# Mezzanine.net
KiCad netlist of a schematic drawn in Altium Designer
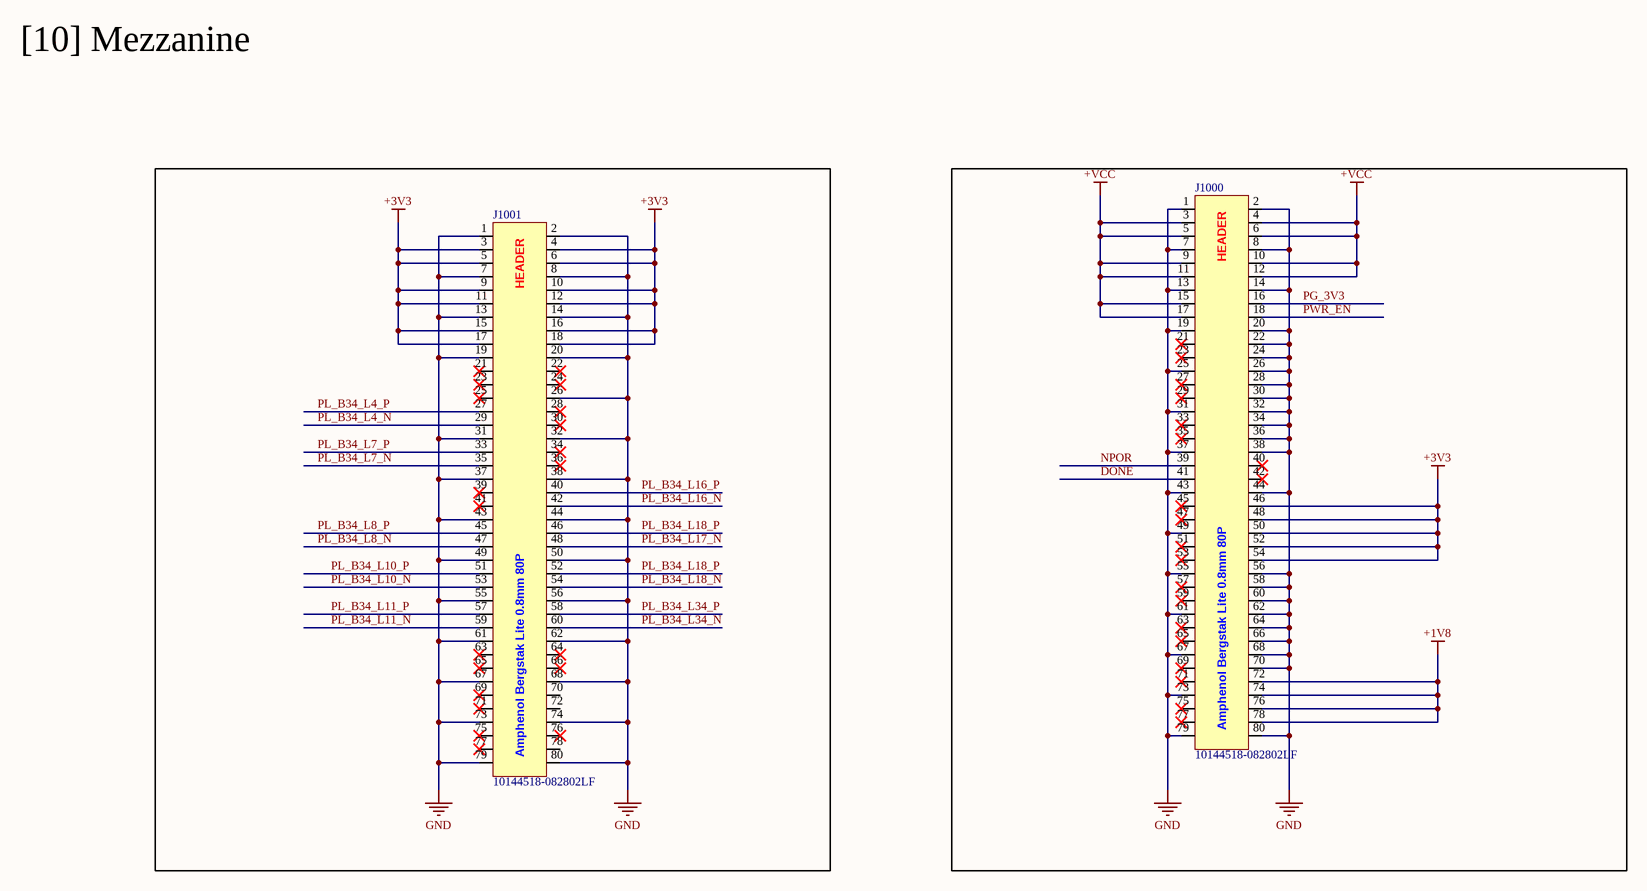
[diagram p0: Mezzanine.SchDoc]

(export (version "E")
  (design (tool "Eeschema 10.0.6"))
  (components
    (comp (ref "J1000")
      (value "10144518-082802LF")
      (footprint "10144518-082802LF")
      (description "BergStak® Lite 0.80mm, Board-to-Board Connector, 80 Positions, Dual Row, Vertical Header")
      (fields (field (name "MANUFACTURER") "Amphenol"))
      (libsource (lib "Schematic-Lib-PhilsLab") (part "10144518-082802LF"))
    )
    (comp (ref "J1001")
      (value "10144518-082802LF")
      (footprint "10144518-082802LF")
      (description "BergStak® Lite 0.80mm, Board-to-Board Connector, 80 Positions, Dual Row, Vertical Header")
      (fields (field (name "MANUFACTURER") "Amphenol"))
      (libsource (lib "Schematic-Lib-PhilsLab") (part "10144518-082802LF"))
    )
  )
  (nets
    (net (code "1") (name "+1V8") (class "Default")
      (node (ref "J1000") (pin "72") (pintype "passive"))
      (node (ref "J1000") (pin "74") (pintype "passive"))
      (node (ref "J1000") (pin "76") (pintype "passive"))
      (node (ref "J1000") (pin "78") (pintype "passive"))
    )
    (net (code "2") (name "+3V3") (class "Default")
      (node (ref "J1000") (pin "46") (pintype "passive"))
      (node (ref "J1000") (pin "48") (pintype "passive"))
      (node (ref "J1000") (pin "50") (pintype "passive"))
      (node (ref "J1000") (pin "52") (pintype "passive"))
      (node (ref "J1000") (pin "54") (pintype "passive"))
      (node (ref "J1001") (pin "10") (pintype "passive"))
      (node (ref "J1001") (pin "11") (pintype "passive"))
      (node (ref "J1001") (pin "12") (pintype "passive"))
      (node (ref "J1001") (pin "15") (pintype "passive"))
      (node (ref "J1001") (pin "16") (pintype "passive"))
      (node (ref "J1001") (pin "17") (pintype "passive"))
      (node (ref "J1001") (pin "18") (pintype "passive"))
      (node (ref "J1001") (pin "3") (pintype "passive"))
      (node (ref "J1001") (pin "4") (pintype "passive"))
      (node (ref "J1001") (pin "5") (pintype "passive"))
      (node (ref "J1001") (pin "6") (pintype "passive"))
      (node (ref "J1001") (pin "9") (pintype "passive"))
    )
    (net (code "3") (name "+VCC") (class "Default")
      (node (ref "J1000") (pin "10") (pintype "passive"))
      (node (ref "J1000") (pin "11") (pintype "passive"))
      (node (ref "J1000") (pin "12") (pintype "passive"))
      (node (ref "J1000") (pin "15") (pintype "passive"))
      (node (ref "J1000") (pin "17") (pintype "passive"))
      (node (ref "J1000") (pin "3") (pintype "passive"))
      (node (ref "J1000") (pin "4") (pintype "passive"))
      (node (ref "J1000") (pin "5") (pintype "passive"))
      (node (ref "J1000") (pin "6") (pintype "passive"))
      (node (ref "J1000") (pin "9") (pintype "passive"))
    )
    (net (code "4") (name "/DONE") (class "Default") (node (ref "J1000") (pin "41") (pintype "passive")))
    (net (code "5") (name "/NPOR") (class "Default") (node (ref "J1000") (pin "39") (pintype "passive")))
    (net (code "6") (name "/PG_3V3") (class "Default") (node (ref "J1000") (pin "16") (pintype "passive")))
    (net (code "7") (name "/PL_B34_L4_N") (class "Default")
      (node (ref "J1001") (pin "29") (pintype "passive"))
    )
    (net (code "8") (name "/PL_B34_L4_P") (class "Default")
      (node (ref "J1001") (pin "27") (pintype "passive"))
    )
    (net (code "9") (name "/PL_B34_L7_N") (class "Default")
      (node (ref "J1001") (pin "35") (pintype "passive"))
    )
    (net (code "10") (name "/PL_B34_L7_P") (class "Default")
      (node (ref "J1001") (pin "33") (pintype "passive"))
    )
    (net (code "11") (name "/PL_B34_L8_N") (class "Default")
      (node (ref "J1001") (pin "47") (pintype "passive"))
    )
    (net (code "12") (name "/PL_B34_L8_P") (class "Default")
      (node (ref "J1001") (pin "45") (pintype "passive"))
    )
    (net (code "13") (name "/PL_B34_L10_N") (class "Default")
      (node (ref "J1001") (pin "53") (pintype "passive"))
    )
    (net (code "14") (name "/PL_B34_L10_P") (class "Default")
      (node (ref "J1001") (pin "51") (pintype "passive"))
    )
    (net (code "15") (name "/PL_B34_L11_N") (class "Default")
      (node (ref "J1001") (pin "59") (pintype "passive"))
    )
    (net (code "16") (name "/PL_B34_L11_P") (class "Default")
      (node (ref "J1001") (pin "57") (pintype "passive"))
    )
    (net (code "17") (name "/PL_B34_L16_N") (class "Default")
      (node (ref "J1001") (pin "42") (pintype "passive"))
    )
    (net (code "18") (name "/PL_B34_L16_P") (class "Default")
      (node (ref "J1001") (pin "40") (pintype "passive"))
    )
    (net (code "19") (name "/PL_B34_L17_N") (class "Default")
      (node (ref "J1001") (pin "48") (pintype "passive"))
    )
    (net (code "20") (name "/PL_B34_L18_N") (class "Default")
      (node (ref "J1001") (pin "54") (pintype "passive"))
    )
    (net (code "21") (name "/PL_B34_L18_P") (class "Default")
      (node (ref "J1001") (pin "46") (pintype "passive"))
      (node (ref "J1001") (pin "52") (pintype "passive"))
    )
    (net (code "22") (name "/PL_B34_L34_N") (class "Default")
      (node (ref "J1001") (pin "60") (pintype "passive"))
    )
    (net (code "23") (name "/PL_B34_L34_P") (class "Default")
      (node (ref "J1001") (pin "58") (pintype "passive"))
    )
    (net (code "24") (name "/PWR_EN") (class "Default") (node (ref "J1000") (pin "18") (pintype "passive")))
    (net (code "25") (name "GND") (class "Default")
      (node (ref "J1000") (pin "1") (pintype "passive"))
      (node (ref "J1000") (pin "13") (pintype "passive"))
      (node (ref "J1000") (pin "14") (pintype "passive"))
      (node (ref "J1000") (pin "19") (pintype "passive"))
      (node (ref "J1000") (pin "2") (pintype "passive"))
      (node (ref "J1000") (pin "20") (pintype "passive"))
      (node (ref "J1000") (pin "22") (pintype "passive"))
      (node (ref "J1000") (pin "24") (pintype "passive"))
      (node (ref "J1000") (pin "25") (pintype "passive"))
      (node (ref "J1000") (pin "26") (pintype "passive"))
      (node (ref "J1000") (pin "28") (pintype "passive"))
      (node (ref "J1000") (pin "30") (pintype "passive"))
      (node (ref "J1000") (pin "31") (pintype "passive"))
      (node (ref "J1000") (pin "32") (pintype "passive"))
      (node (ref "J1000") (pin "34") (pintype "passive"))
      (node (ref "J1000") (pin "36") (pintype "passive"))
      (node (ref "J1000") (pin "37") (pintype "passive"))
      (node (ref "J1000") (pin "38") (pintype "passive"))
      (node (ref "J1000") (pin "43") (pintype "passive"))
      (node (ref "J1000") (pin "44") (pintype "passive"))
      (node (ref "J1000") (pin "49") (pintype "passive"))
      (node (ref "J1000") (pin "55") (pintype "passive"))
      (node (ref "J1000") (pin "56") (pintype "passive"))
      (node (ref "J1000") (pin "58") (pintype "passive"))
      (node (ref "J1000") (pin "60") (pintype "passive"))
      (node (ref "J1000") (pin "61") (pintype "passive"))
      (node (ref "J1000") (pin "62") (pintype "passive"))
      (node (ref "J1000") (pin "64") (pintype "passive"))
      (node (ref "J1000") (pin "66") (pintype "passive"))
      (node (ref "J1000") (pin "67") (pintype "passive"))
      (node (ref "J1000") (pin "68") (pintype "passive"))
      (node (ref "J1000") (pin "7") (pintype "passive"))
      (node (ref "J1000") (pin "70") (pintype "passive"))
      (node (ref "J1000") (pin "73") (pintype "passive"))
      (node (ref "J1000") (pin "79") (pintype "passive"))
      (node (ref "J1000") (pin "8") (pintype "passive"))
      (node (ref "J1000") (pin "80") (pintype "passive"))
      (node (ref "J1001") (pin "1") (pintype "passive"))
      (node (ref "J1001") (pin "13") (pintype "passive"))
      (node (ref "J1001") (pin "14") (pintype "passive"))
      (node (ref "J1001") (pin "19") (pintype "passive"))
      (node (ref "J1001") (pin "2") (pintype "passive"))
      (node (ref "J1001") (pin "20") (pintype "passive"))
      (node (ref "J1001") (pin "26") (pintype "passive"))
      (node (ref "J1001") (pin "31") (pintype "passive"))
      (node (ref "J1001") (pin "32") (pintype "passive"))
      (node (ref "J1001") (pin "37") (pintype "passive"))
      (node (ref "J1001") (pin "38") (pintype "passive"))
      (node (ref "J1001") (pin "43") (pintype "passive"))
      (node (ref "J1001") (pin "44") (pintype "passive"))
      (node (ref "J1001") (pin "49") (pintype "passive"))
      (node (ref "J1001") (pin "50") (pintype "passive"))
      (node (ref "J1001") (pin "55") (pintype "passive"))
      (node (ref "J1001") (pin "56") (pintype "passive"))
      (node (ref "J1001") (pin "61") (pintype "passive"))
      (node (ref "J1001") (pin "62") (pintype "passive"))
      (node (ref "J1001") (pin "67") (pintype "passive"))
      (node (ref "J1001") (pin "68") (pintype "passive"))
      (node (ref "J1001") (pin "7") (pintype "passive"))
      (node (ref "J1001") (pin "73") (pintype "passive"))
      (node (ref "J1001") (pin "74") (pintype "passive"))
      (node (ref "J1001") (pin "79") (pintype "passive"))
      (node (ref "J1001") (pin "8") (pintype "passive"))
      (node (ref "J1001") (pin "80") (pintype "passive"))
    )
    (net (code "26") (name "unconnected-(J1000-Pad21)") (class "Default")
      (node (ref "J1000") (pin "21") (pintype "passive+no_connect"))
    )
    (net (code "27") (name "unconnected-(J1000-Pad23)") (class "Default")
      (node (ref "J1000") (pin "23") (pintype "passive+no_connect"))
    )
    (net (code "28") (name "unconnected-(J1000-Pad27)") (class "Default")
      (node (ref "J1000") (pin "27") (pintype "passive+no_connect"))
    )
    (net (code "29") (name "unconnected-(J1000-Pad29)") (class "Default")
      (node (ref "J1000") (pin "29") (pintype "passive+no_connect"))
    )
    (net (code "30") (name "unconnected-(J1000-Pad33)") (class "Default")
      (node (ref "J1000") (pin "33") (pintype "passive+no_connect"))
    )
    (net (code "31") (name "unconnected-(J1000-Pad35)") (class "Default")
      (node (ref "J1000") (pin "35") (pintype "passive+no_connect"))
    )
    (net (code "32") (name "unconnected-(J1000-Pad40)") (class "Default")
      (node (ref "J1000") (pin "40") (pintype "passive+no_connect"))
    )
    (net (code "33") (name "unconnected-(J1000-Pad42)") (class "Default")
      (node (ref "J1000") (pin "42") (pintype "passive+no_connect"))
    )
    (net (code "34") (name "unconnected-(J1000-Pad45)") (class "Default")
      (node (ref "J1000") (pin "45") (pintype "passive+no_connect"))
    )
    (net (code "35") (name "unconnected-(J1000-Pad47)") (class "Default")
      (node (ref "J1000") (pin "47") (pintype "passive+no_connect"))
    )
    (net (code "36") (name "unconnected-(J1000-Pad51)") (class "Default")
      (node (ref "J1000") (pin "51") (pintype "passive+no_connect"))
    )
    (net (code "37") (name "unconnected-(J1000-Pad53)") (class "Default")
      (node (ref "J1000") (pin "53") (pintype "passive+no_connect"))
    )
    (net (code "38") (name "unconnected-(J1000-Pad57)") (class "Default")
      (node (ref "J1000") (pin "57") (pintype "passive+no_connect"))
    )
    (net (code "39") (name "unconnected-(J1000-Pad59)") (class "Default")
      (node (ref "J1000") (pin "59") (pintype "passive+no_connect"))
    )
    (net (code "40") (name "unconnected-(J1000-Pad63)") (class "Default")
      (node (ref "J1000") (pin "63") (pintype "passive+no_connect"))
    )
    (net (code "41") (name "unconnected-(J1000-Pad65)") (class "Default")
      (node (ref "J1000") (pin "65") (pintype "passive+no_connect"))
    )
    (net (code "42") (name "unconnected-(J1000-Pad69)") (class "Default")
      (node (ref "J1000") (pin "69") (pintype "passive+no_connect"))
    )
    (net (code "43") (name "unconnected-(J1000-Pad71)") (class "Default")
      (node (ref "J1000") (pin "71") (pintype "passive+no_connect"))
    )
    (net (code "44") (name "unconnected-(J1000-Pad75)") (class "Default")
      (node (ref "J1000") (pin "75") (pintype "passive+no_connect"))
    )
    (net (code "45") (name "unconnected-(J1000-Pad77)") (class "Default")
      (node (ref "J1000") (pin "77") (pintype "passive+no_connect"))
    )
    (net (code "46") (name "unconnected-(J1001-Pad21)") (class "Default")
      (node (ref "J1001") (pin "21") (pintype "passive+no_connect"))
    )
    (net (code "47") (name "unconnected-(J1001-Pad22)") (class "Default")
      (node (ref "J1001") (pin "22") (pintype "passive+no_connect"))
    )
    (net (code "48") (name "unconnected-(J1001-Pad23)") (class "Default")
      (node (ref "J1001") (pin "23") (pintype "passive+no_connect"))
    )
    (net (code "49") (name "unconnected-(J1001-Pad24)") (class "Default")
      (node (ref "J1001") (pin "24") (pintype "passive+no_connect"))
    )
    (net (code "50") (name "unconnected-(J1001-Pad25)") (class "Default")
      (node (ref "J1001") (pin "25") (pintype "passive+no_connect"))
    )
    (net (code "51") (name "unconnected-(J1001-Pad28)") (class "Default")
      (node (ref "J1001") (pin "28") (pintype "passive+no_connect"))
    )
    (net (code "52") (name "unconnected-(J1001-Pad30)") (class "Default")
      (node (ref "J1001") (pin "30") (pintype "passive+no_connect"))
    )
    (net (code "53") (name "unconnected-(J1001-Pad34)") (class "Default")
      (node (ref "J1001") (pin "34") (pintype "passive+no_connect"))
    )
    (net (code "54") (name "unconnected-(J1001-Pad36)") (class "Default")
      (node (ref "J1001") (pin "36") (pintype "passive+no_connect"))
    )
    (net (code "55") (name "unconnected-(J1001-Pad39)") (class "Default")
      (node (ref "J1001") (pin "39") (pintype "passive+no_connect"))
    )
    (net (code "56") (name "unconnected-(J1001-Pad41)") (class "Default")
      (node (ref "J1001") (pin "41") (pintype "passive+no_connect"))
    )
    (net (code "57") (name "unconnected-(J1001-Pad63)") (class "Default")
      (node (ref "J1001") (pin "63") (pintype "passive+no_connect"))
    )
    (net (code "58") (name "unconnected-(J1001-Pad64)") (class "Default")
      (node (ref "J1001") (pin "64") (pintype "passive+no_connect"))
    )
    (net (code "59") (name "unconnected-(J1001-Pad65)") (class "Default")
      (node (ref "J1001") (pin "65") (pintype "passive+no_connect"))
    )
    (net (code "60") (name "unconnected-(J1001-Pad66)") (class "Default")
      (node (ref "J1001") (pin "66") (pintype "passive+no_connect"))
    )
    (net (code "61") (name "unconnected-(J1001-Pad69)") (class "Default")
      (node (ref "J1001") (pin "69") (pintype "passive+no_connect"))
    )
    (net (code "62") (name "unconnected-(J1001-Pad70)") (class "Default")
      (node (ref "J1001") (pin "70") (pintype "passive"))
    )
    (net (code "63") (name "unconnected-(J1001-Pad71)") (class "Default")
      (node (ref "J1001") (pin "71") (pintype "passive+no_connect"))
    )
    (net (code "64") (name "unconnected-(J1001-Pad72)") (class "Default")
      (node (ref "J1001") (pin "72") (pintype "passive"))
    )
    (net (code "65") (name "unconnected-(J1001-Pad75)") (class "Default")
      (node (ref "J1001") (pin "75") (pintype "passive+no_connect"))
    )
    (net (code "66") (name "unconnected-(J1001-Pad76)") (class "Default")
      (node (ref "J1001") (pin "76") (pintype "passive+no_connect"))
    )
    (net (code "67") (name "unconnected-(J1001-Pad77)") (class "Default")
      (node (ref "J1001") (pin "77") (pintype "passive+no_connect"))
    )
    (net (code "68") (name "unconnected-(J1001-Pad78)") (class "Default")
      (node (ref "J1001") (pin "78") (pintype "passive"))
    )
  )
)
